# Booster_PA_PREAMP_HL.net
KiCad netlist of a schematic drawn in Altium Designer
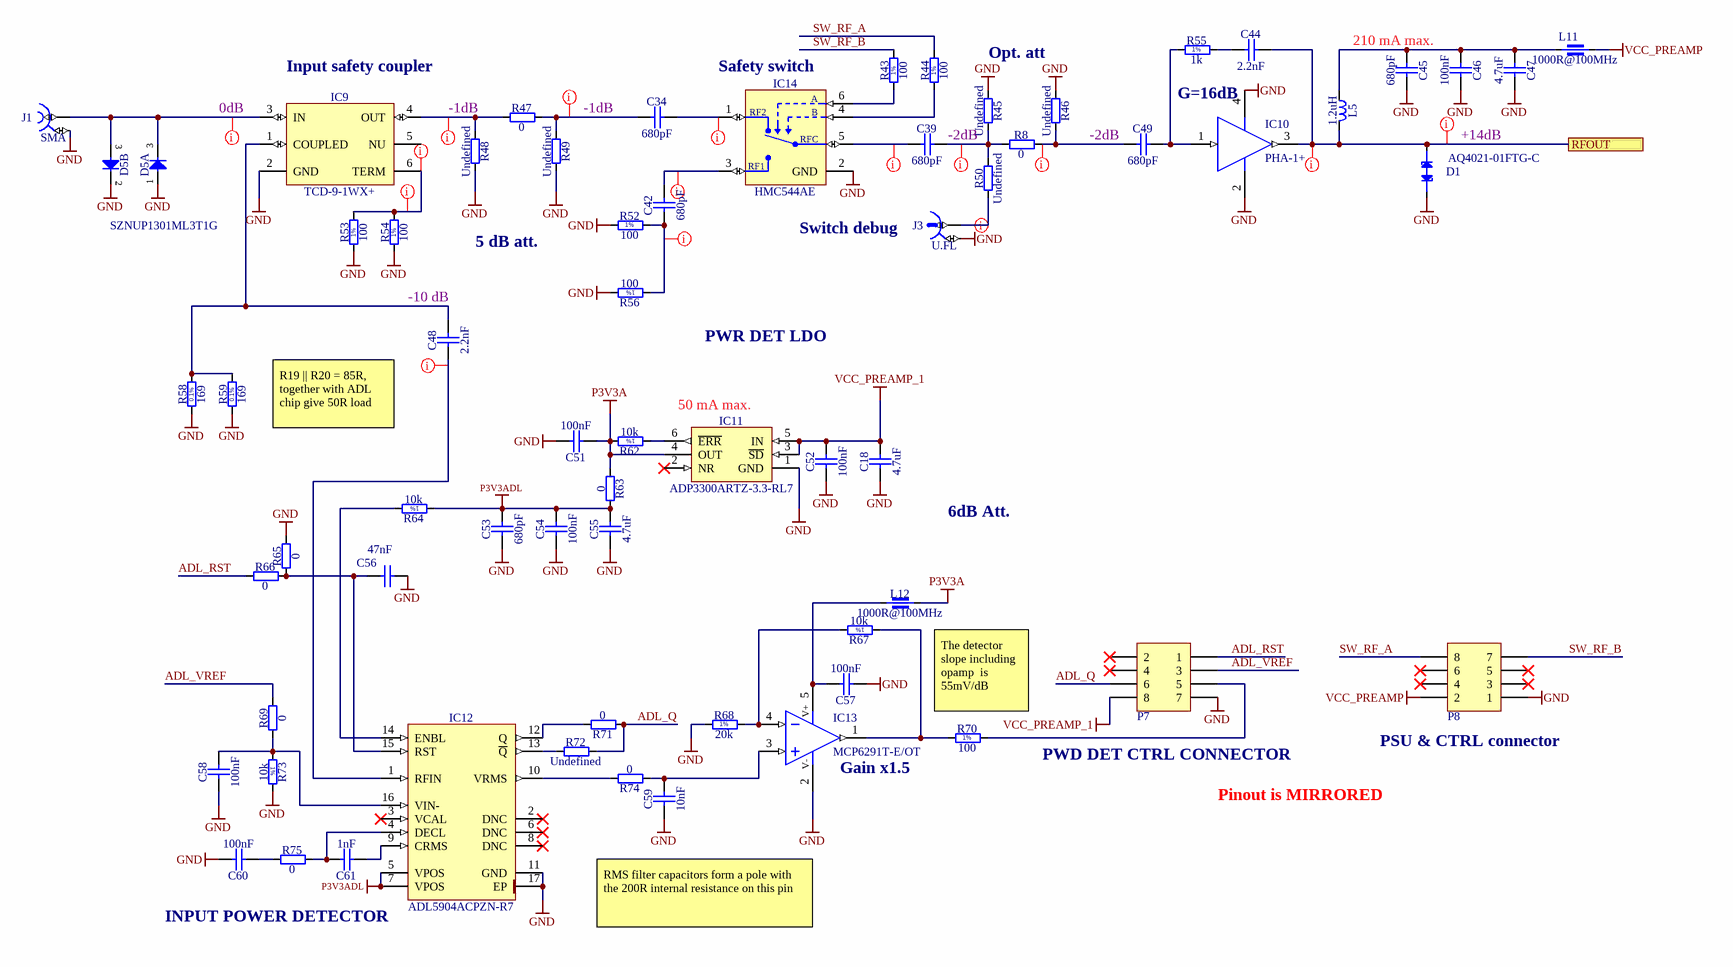
[diagram p0: Booster_PA_PREAMP_HL.SchDoc]

(export (version "E")
  (design (tool "Eeschema 10.0.6"))
  (components
    (comp (ref "C18")
      (value "4.7uF")
      (footprint "CAPC1709X95N")
      (description "Non-polarised capacitor")
      (fields
        (field (name "MANUFACTURER") "GENERIC")
        (field (name "MANUFACTURER PART NUMBER") "CC0603_4.7UF_16V_10%_X5R")
        (field (name "AUTHOR") "CERN DEM JLC")
      )
      (libsource (lib "Capacitors") (part "Capacitor - non polarized"))
    )
    (comp (ref "C34")
      (value "680pF")
      (footprint "CAPC1608X87N")
      (description "Non-polarised capacitor")
      (fields
        (field (name "PART NUMBER") "CC0603_680PF_50V_5%_NP0")
        (field (name "VOLTAGE") "50V")
        (field (name "AUTHOR") "CERN DEM JLC")
      )
      (libsource (lib "Capacitors") (part "Capacitor - non polarized"))
    )
    (comp (ref "C39")
      (value "680pF")
      (footprint "CAPC1608X87N")
      (description "Non-polarised capacitor")
      (fields
        (field (name "PART NUMBER") "CC0603_680PF_50V_5%_NP0")
        (field (name "VOLTAGE") "50V")
        (field (name "AUTHOR") "CERN DEM JLC")
      )
      (libsource (lib "Capacitors") (part "Capacitor - non polarized"))
    )
    (comp (ref "C42")
      (value "680pF")
      (footprint "CAPC1608X87N")
      (description "Non-polarised capacitor")
      (fields
        (field (name "PART NUMBER") "CC0603_680PF_50V_5%_NP0")
        (field (name "VOLTAGE") "50V")
        (field (name "AUTHOR") "CERN DEM JLC")
      )
      (libsource (lib "Capacitors") (part "Capacitor - non polarized"))
    )
    (comp (ref "C44")
      (value "2.2nF")
      (footprint "CAPC1608X87N")
      (description "Non-polarised capacitor")
      (fields
        (field (name "PART NUMBER") "CC0603_2.2NF_50V_5%_C0G")
        (field (name "VOLTAGE") "50V")
        (field (name "AUTHOR") "CERN DEM JMW")
      )
      (libsource (lib "Capacitors") (part "Capacitor - non polarized"))
    )
    (comp (ref "C45")
      (value "680pF")
      (footprint "CAPC1608X87N")
      (description "Non-polarised capacitor")
      (fields
        (field (name "MANUFACTURER") "GENERIC")
        (field (name "MANUFACTURER PART NUMBER") "CC0603_680PF_50V_5%_NP0")
        (field (name "AUTHOR") "CERN DEM JLC")
      )
      (libsource (lib "Capacitors") (part "Capacitor - non polarized"))
    )
    (comp (ref "C46")
      (value "100nF")
      (footprint "CAPC1608X87N")
      (description "Non-polarised capacitor")
      (fields
        (field (name "MANUFACTURER") "GENERIC")
        (field (name "MANUFACTURER PART NUMBER") "CC0603_100NF_50V_10%_X7R")
        (field (name "AUTHOR") "CERN DEM JLC")
      )
      (libsource (lib "Capacitors") (part "Capacitor - non polarized"))
    )
    (comp (ref "C47")
      (value "4.7uF")
      (footprint "CAPC1709X95N")
      (description "Non-polarised capacitor")
      (fields
        (field (name "MANUFACTURER") "GENERIC")
        (field (name "MANUFACTURER PART NUMBER") "CC0603_4.7UF_16V_10%_X5R")
        (field (name "AUTHOR") "CERN DEM JLC")
      )
      (libsource (lib "Capacitors") (part "Capacitor - non polarized"))
    )
    (comp (ref "C48")
      (value "2.2nF")
      (footprint "CAPC1608X87N")
      (description "Non-polarised capacitor")
      (fields
        (field (name "PART NUMBER") "CC0603_2.2NF_50V_5%_C0G")
        (field (name "VOLTAGE") "50V")
        (field (name "AUTHOR") "CERN DEM JMW")
      )
      (libsource (lib "Capacitors") (part "Capacitor - non polarized"))
    )
    (comp (ref "C49")
      (value "680pF")
      (footprint "CAPC1608X87N")
      (description "Non-polarised capacitor")
      (fields
        (field (name "MANUFACTURER") "GENERIC")
        (field (name "MANUFACTURER PART NUMBER") "CC0603_680PF_50V_5%_NP0")
        (field (name "AUTHOR") "CERN DEM JLC")
      )
      (libsource (lib "Capacitors") (part "Capacitor - non polarized"))
    )
    (comp (ref "C51")
      (value "100nF")
      (footprint "CAPC1608X87N")
      (description "Non-polarised capacitor")
      (fields
        (field (name "MANUFACTURER") "GENERIC")
        (field (name "MANUFACTURER PART NUMBER") "CC0603_100NF_50V_10%_X7R")
        (field (name "AUTHOR") "CERN DEM JLC")
      )
      (libsource (lib "Capacitors") (part "Capacitor - non polarized"))
    )
    (comp (ref "C52")
      (value "100nF")
      (footprint "CAPC1608X87N")
      (description "Non-polarised capacitor")
      (fields
        (field (name "MANUFACTURER") "GENERIC")
        (field (name "MANUFACTURER PART NUMBER") "CC0603_100NF_50V_10%_X7R")
        (field (name "AUTHOR") "CERN DEM JLC")
      )
      (libsource (lib "Capacitors") (part "Capacitor - non polarized"))
    )
    (comp (ref "C53")
      (value "680pF")
      (footprint "CAPC1608X87N")
      (description "Non-polarised capacitor")
      (fields
        (field (name "MANUFACTURER") "GENERIC")
        (field (name "MANUFACTURER PART NUMBER") "CC0603_680PF_50V_5%_NP0")
        (field (name "AUTHOR") "CERN DEM JLC")
      )
      (libsource (lib "Capacitors") (part "Capacitor - non polarized"))
    )
    (comp (ref "C54")
      (value "100nF")
      (footprint "CAPC1608X87N")
      (description "Non-polarised capacitor")
      (fields
        (field (name "MANUFACTURER") "GENERIC")
        (field (name "MANUFACTURER PART NUMBER") "CC0603_100NF_50V_10%_X7R")
        (field (name "AUTHOR") "CERN DEM JLC")
      )
      (libsource (lib "Capacitors") (part "Capacitor - non polarized"))
    )
    (comp (ref "C55")
      (value "4.7uF")
      (footprint "CAPC1709X95N")
      (description "Non-polarised capacitor")
      (fields
        (field (name "MANUFACTURER") "GENERIC")
        (field (name "MANUFACTURER PART NUMBER") "CC0603_4.7UF_16V_10%_X5R")
        (field (name "AUTHOR") "CERN DEM JLC")
      )
      (libsource (lib "Capacitors") (part "Capacitor - non polarized"))
    )
    (comp (ref "C56")
      (value "47nF")
      (footprint "CAPC1608X87N")
      (description "Non-polarised capacitor")
      (fields
        (field (name "PART NUMBER") "CC0603_47NF_25V_10%_X7R")
        (field (name "VOLTAGE") "25V")
        (field (name "AUTHOR") "CERN DEM JLC")
      )
      (libsource (lib "Capacitors") (part "Capacitor - non polarized"))
    )
    (comp (ref "C57")
      (value "100nF")
      (footprint "CAPC1608X87N")
      (description "Non-polarised capacitor")
      (fields
        (field (name "MANUFACTURER") "GENERIC")
        (field (name "MANUFACTURER PART NUMBER") "CC0603_100NF_50V_10%_X7R")
        (field (name "AUTHOR") "CERN DEM JLC")
      )
      (libsource (lib "Capacitors") (part "Capacitor - non polarized"))
    )
    (comp (ref "C58")
      (value "100nF")
      (footprint "CAPC1608X87N")
      (description "Non-polarised capacitor")
      (fields
        (field (name "MANUFACTURER") "GENERIC")
        (field (name "MANUFACTURER PART NUMBER") "CC0603_100NF_50V_10%_X7R")
        (field (name "AUTHOR") "CERN DEM JLC")
      )
      (libsource (lib "Capacitors") (part "Capacitor - non polarized"))
    )
    (comp (ref "C59")
      (value "10nF")
      (footprint "CAPC1005X55N")
      (description "Non-polarised capacitor")
      (fields
        (field (name "MANUFACTURER") "GENERIC")
        (field (name "MANUFACTURER PART NUMBER") "CC0402_10NF_25V_10%_X7R")
        (field (name "AUTHOR") "CERN DEM JLC")
      )
      (libsource (lib "Capacitors") (part "Capacitor - non polarized"))
    )
    (comp (ref "C60")
      (value "100nF")
      (footprint "CAPC1608X87N")
      (description "Non-polarised capacitor")
      (fields
        (field (name "MANUFACTURER") "GENERIC")
        (field (name "MANUFACTURER PART NUMBER") "CC0603_100NF_50V_10%_X7R")
        (field (name "AUTHOR") "CERN DEM JLC")
      )
      (libsource (lib "Capacitors") (part "Capacitor - non polarized"))
    )
    (comp (ref "C61")
      (value "1nF")
      (footprint "CAPC1005X55N")
      (description "Non-polarised capacitor")
      (fields
        (field (name "PART NUMBER") "CC0402_1NF_50V_10%_X7R")
        (field (name "VOLTAGE") "50V")
        (field (name "AUTHOR") "CERN DEM JLC")
      )
      (libsource (lib "Capacitors") (part "Capacitor - non polarized"))
    )
    (comp (ref "D1")
      (value "AQ4021-01FTG-C")
      (footprint "SOD2513X114N")
      (description "6V Bi-directional,ESD Protection for Transient Voltage Suppressor Diode")
      (fields (field (name "VOLTAGE") "6V") (field (name "POWER") "450W") (field (name "AUTHOR") "GK"))
      (libsource (lib "Diodes") (part "D_TVS_AQ4021-01FTG-C"))
    )
    (comp (ref "D5")
      (value "SZNUP1301ML3T1G")
      (footprint "SOT95P240X110-3N")
      (description "Low Capacitance Diode Array for ESD Protection in a Single Data Line")
      (fields (field (name "VOLTAGE") "70V") (field (name "POWER") "215mA") (field (name "AUTHOR") "GK"))
      (libsource (lib "Diodes") (part "D_TVS_SZNUP1301ML3T1G"))
    )
    (comp (ref "IC9")
      (value "TCD-9-1WX+")
      (footprint "MINI-CIRCUITS_DB1627")
      (description "50 Ohm, 5 To 2000MHz, Directional Coupler")
      (fields (field (name "MANUFACTURER") "MINI-CIRCUITS") (field (name "AUTHOR") "CERN DEM BC"))
      (libsource (lib "ICs And Semiconductors") (part "TCD-9-1W"))
    )
    (comp (ref "IC10")
      (value "PHA-1+")
      (footprint "MINI-CIRCUITS_DF782")
      (description "Monolithic Amplifier")
      (fields (field (name "MANUFACTURER") "MINI-CIRCUITS") (field (name "AUTHOR") "CERN DEM BC"))
      (libsource (lib "ICs And Semiconductors") (part "Monolithic Amplifier Type 1"))
    )
    (comp (ref "IC11")
      (value "ADP3300ARTZ-3.3-RL7")
      (footprint "SOT95P280X145-6N")
      (description "High Accuracy anyCAP® 50 mA Low Dropout Linear Regulator")
      (fields (field (name "MANUFACTURER") "ANALOG DEVICES") (field (name "AUTHOR") "CERN DEM JLC"))
      (libsource (lib "ICs And Semiconductors") (part "ADP3300ARTZ"))
    )
    (comp (ref "IC12")
      (value "ADL5904ACPZN-R7")
      (footprint "QFN50P300X300X80-17N-S175")
      (description "DC to 6 GHz, 45 dB TruPwr Detector With Envelope Threshold Detection")
      (fields (field (name "MANUFACTURER") "ANALOG DEVICES") (field (name "AUTHOR") "CERN DEM MR"))
      (libsource (lib "ICs And Semiconductors") (part "ADL5904"))
    )
    (comp (ref "IC13")
      (value "MCP6291T-E/OT")
      (footprint "SOT95P270X145-5N")
      (description "Operational Amplifier")
      (fields (field (name "MANUFACTURER") "MICROCHIP TECHNOLOGY") (field (name "AUTHOR") "CERN DEM BC"))
      (libsource (lib "ICs And Semiconductors") (part "Operational Amplifier Type7"))
    )
    (comp (ref "IC14")
      (value "HMC544AE")
      (footprint "SOT95P280X145-6N")
      (description "GaAs MMIC T/R Switch DC - 4 GHz")
      (fields (field (name "MANUFACTURER") "ANALOG DEVICES") (field (name "AUTHOR") "CERN DEM MR"))
      (libsource (lib "ICs And Semiconductors") (part "HMC544AE"))
    )
    (comp (ref "J1")
      (value "SMA")
      (footprint "LINK_CONSMA002-SMD-G")
      (fields
        (field (name "PART NUMBER") "LINK_CONSMA002-SMD-G")
        (field (name "MANUFACTURER") "LINK TECHNOLOGIES")
        (field (name "MANUFACTURER PART NUMBER") "CONSMA002-SMD-G")
        (field (name "AUTHOR") "CERN DEM BC")
      )
      (libsource (lib "Connectors") (part "Coax_1Female_1Shield"))
    )
    (comp (ref "J3")
      (value "U.FL")
      (footprint "HIROSE_U.FL-R-SMT-1(10)")
      (fields
        (field (name "PART NUMBER") "HIROSE_U.FL-R-SMT-1(10)")
        (field (name "MANUFACTURER") "HIROSE (HRS)")
        (field (name "MANUFACTURER PART NUMBER") "U.FL-R-SMT-1(10)")
        (field (name "AUTHOR") "CERN DEM JLC")
      )
      (libsource (lib "Connectors") (part "Coax_1Male_1Shield"))
    )
    (comp (ref "L5")
      (value "1.2uH")
      (footprint "IND_TDK_ADL2012")
      (description "Inductor")
      (fields
        (field (name "PART NUMBER") "IND0805_TDK_ADL2012S-1R2M-T01")
        (field (name "POWER") "400mA")
        (field (name "AUTHOR") "GK")
      )
      (libsource (lib "Inductors_Transformers") (part "IND0805_TDK_ADL2012S-1R2M-T01"))
    )
    (comp (ref "L11")
      (value "1000R@100MHz")
      (footprint "INDC1608X95N")
      (fields
        (field (name "MANUFACTURER") "MURATA")
        (field (name "MANUFACTURER PART NUMBER") "BLM18HE102SN1")
        (field (name "PART NUMBER") "IND0603_MURATA_BLM18HE102SN1")
        (field (name "AUTHOR") "CERN DEM JLC")
      )
      (libsource (lib "Inductors & Transformers") (part "Ferrite Bead"))
    )
    (comp (ref "L12")
      (value "1000R@100MHz")
      (footprint "INDC1608X95N")
      (fields
        (field (name "MANUFACTURER") "MURATA")
        (field (name "MANUFACTURER PART NUMBER") "BLM18HE102SN1")
        (field (name "PART NUMBER") "IND0603_MURATA_BLM18HE102SN1")
        (field (name "AUTHOR") "CERN DEM JLC")
      )
      (libsource (lib "Inductors & Transformers") (part "Ferrite Bead"))
    )
    (comp (ref "P7")
      (value "ZL264-8DG")
      (footprint "HDR2X4_SMD")
      (description "Header, 4-Pin, Dual Row")
      (libsource (lib "onyks") (part "HDR2X4"))
    )
    (comp (ref "P8")
      (value "ZL264-8DG")
      (footprint "HDR2X4_SMD")
      (description "Header, 4-Pin, Dual Row")
      (libsource (lib "") (part "HDR2X4_1"))
    )
    (comp (ref "R8")
      (value "0")
      (footprint "RESC1608X55N")
      (description "Resistor")
      (fields
        (field (name "MANUFACTURER") "GENERIC")
        (field (name "MANUFACTURER PART NUMBER") "R0603_0R_JUMPER")
        (field (name "AUTHOR") "CERN DEM JLC")
      )
      (libsource (lib "Resistors") (part "Resistor"))
    )
    (comp (ref "R43")
      (value "100")
      (footprint "RESC1608X55N")
      (description "Resistor - 1%")
      (fields
        (field (name "MANUFACTURER") "GENERIC")
        (field (name "MANUFACTURER PART NUMBER") "R0603_100R_1%_0.1W_100PPM")
        (field (name "AUTHOR") "CERN DEM JLC")
      )
      (libsource (lib "Resistors") (part "Resistor - 1%"))
    )
    (comp (ref "R44")
      (value "100")
      (footprint "RESC1608X55N")
      (description "Resistor - 1%")
      (fields
        (field (name "MANUFACTURER") "GENERIC")
        (field (name "MANUFACTURER PART NUMBER") "R0603_100R_1%_0.1W_100PPM")
        (field (name "AUTHOR") "CERN DEM JLC")
      )
      (libsource (lib "Resistors") (part "Resistor - 1%"))
    )
    (comp (ref "R45")
      (value "Undefined")
      (footprint "RESC1608X55N")
      (description "Resistor")
      (fields
        (field (name "MANUFACTURER PART NUMBER") "R0603_NO-VALUE")
        (field (name "AUTHOR") "CERN DEM JLC")
      )
      (libsource (lib "Resistors") (part "Resistor"))
    )
    (comp (ref "R46")
      (value "Undefined")
      (footprint "RESC1608X55N")
      (description "Resistor")
      (fields
        (field (name "MANUFACTURER PART NUMBER") "R0603_NO-VALUE")
        (field (name "AUTHOR") "CERN DEM JLC")
      )
      (libsource (lib "Resistors") (part "Resistor"))
    )
    (comp (ref "R47")
      (value "0")
      (footprint "RESC1608X55N")
      (description "Resistor")
      (fields
        (field (name "PART NUMBER") "R0603_0R_JUMPER")
        (field (name "MANUFACTURER") "GENERIC")
        (field (name "AUTHOR") "CERN DEM JLC")
      )
      (libsource (lib "Resistors") (part "Resistor"))
    )
    (comp (ref "R48")
      (value "Undefined")
      (footprint "RESC1608X55N")
      (description "Resistor")
      (fields
        (field (name "MANUFACTURER PART NUMBER") "R0603_NO-VALUE")
        (field (name "AUTHOR") "CERN DEM JLC")
      )
      (libsource (lib "Resistors") (part "Resistor"))
    )
    (comp (ref "R49")
      (value "Undefined")
      (footprint "RESC1608X55N")
      (description "Resistor")
      (fields
        (field (name "MANUFACTURER PART NUMBER") "R0603_NO-VALUE")
        (field (name "AUTHOR") "CERN DEM JLC")
      )
      (libsource (lib "Resistors") (part "Resistor"))
    )
    (comp (ref "R50")
      (value "Undefined")
      (footprint "RESC1608X55N")
      (description "Resistor")
      (fields
        (field (name "MANUFACTURER PART NUMBER") "R0603_NO-VALUE")
        (field (name "AUTHOR") "CERN DEM JLC")
      )
      (libsource (lib "Resistors") (part "Resistor"))
    )
    (comp (ref "R52")
      (value "100")
      (footprint "RESC1608X55N")
      (description "Resistor - 1%")
      (fields
        (field (name "MANUFACTURER") "GENERIC")
        (field (name "MANUFACTURER PART NUMBER") "R0603_100R_1%_0.1W_100PPM")
        (field (name "AUTHOR") "CERN DEM JLC")
      )
      (libsource (lib "Resistors") (part "Resistor - 1%"))
    )
    (comp (ref "R53")
      (value "100")
      (footprint "RESC1608X55N")
      (description "Resistor - 1%")
      (fields
        (field (name "MANUFACTURER") "GENERIC")
        (field (name "MANUFACTURER PART NUMBER") "R0603_100R_1%_0.1W_100PPM")
        (field (name "AUTHOR") "CERN DEM JLC")
      )
      (libsource (lib "Resistors") (part "Resistor - 1%"))
    )
    (comp (ref "R54")
      (value "100")
      (footprint "RESC1608X55N")
      (description "Resistor - 1%")
      (fields
        (field (name "MANUFACTURER") "GENERIC")
        (field (name "MANUFACTURER PART NUMBER") "R0603_100R_1%_0.1W_100PPM")
        (field (name "AUTHOR") "CERN DEM JLC")
      )
      (libsource (lib "Resistors") (part "Resistor - 1%"))
    )
    (comp (ref "R55")
      (value "1k")
      (footprint "RESC1608X55N")
      (description "Resistor - 1%")
      (fields
        (field (name "MANUFACTURER") "GENERIC")
        (field (name "MANUFACTURER PART NUMBER") "R0603_1K_1%_0.1W_100PPM")
        (field (name "AUTHOR") "CERN DEM JLC")
      )
      (libsource (lib "Resistors") (part "Resistor - 1%"))
    )
    (comp (ref "R56")
      (value "100")
      (footprint "RESC1608X55N")
      (description "Resistor - 1%")
      (fields
        (field (name "MANUFACTURER") "GENERIC")
        (field (name "MANUFACTURER PART NUMBER") "R0603_100R_1%_0.1W_100PPM")
        (field (name "AUTHOR") "CERN DEM JLC")
      )
      (libsource (lib "Resistors") (part "Resistor - 1%"))
    )
    (comp (ref "R58")
      (value "169")
      (footprint "RESC1608X55N")
      (description "Resistor - 0.1%")
      (fields
        (field (name "PART NUMBER") "R0603_169R_0.1%_0.063W_10PPM")
        (field (name "POWER") "0.063W")
        (field (name "AUTHOR") "CERN DEM JLC")
      )
      (libsource (lib "Resistors") (part "Resistor - 0.1%"))
    )
    (comp (ref "R59")
      (value "169")
      (footprint "RESC1608X55N")
      (description "Resistor - 0.1%")
      (fields
        (field (name "PART NUMBER") "R0603_169R_0.1%_0.063W_10PPM")
        (field (name "POWER") "0.063W")
        (field (name "AUTHOR") "CERN DEM JLC")
      )
      (libsource (lib "Resistors") (part "Resistor - 0.1%"))
    )
    (comp (ref "R62")
      (value "10k")
      (footprint "RESC1005X40N")
      (description "Resistor - 1%")
      (fields
        (field (name "MANUFACTURER") "GENERIC")
        (field (name "MANUFACTURER PART NUMBER") "R0402_10K_1%_0.0625W_100PPM")
        (field (name "AUTHOR") "CERN DEM JLC")
      )
      (libsource (lib "Resistors") (part "Resistor - 1%"))
    )
    (comp (ref "R63")
      (value "0")
      (footprint "RESC1005X40N")
      (description "Resistor")
      (fields
        (field (name "MANUFACTURER") "GENERIC")
        (field (name "MANUFACTURER PART NUMBER") "R0402_0R_JUMPER")
        (field (name "AUTHOR") "CERN DEM JLC")
      )
      (libsource (lib "Resistors") (part "Resistor"))
    )
    (comp (ref "R64")
      (value "10k")
      (footprint "RESC1005X40N")
      (description "Resistor - 1%")
      (fields
        (field (name "MANUFACTURER") "GENERIC")
        (field (name "MANUFACTURER PART NUMBER") "R0402_10K_1%_0.0625W_100PPM")
        (field (name "AUTHOR") "CERN DEM JLC")
      )
      (libsource (lib "Resistors") (part "Resistor - 1%"))
    )
    (comp (ref "R65")
      (value "0")
      (footprint "RESC1608X55N")
      (description "Resistor")
      (fields
        (field (name "MANUFACTURER") "GENERIC")
        (field (name "MANUFACTURER PART NUMBER") "R0603_0R_JUMPER")
        (field (name "AUTHOR") "CERN DEM JLC")
      )
      (libsource (lib "Resistors") (part "Resistor"))
    )
    (comp (ref "R66")
      (value "0")
      (footprint "RESC1005X40N")
      (description "Resistor")
      (fields
        (field (name "MANUFACTURER") "GENERIC")
        (field (name "MANUFACTURER PART NUMBER") "R0402_0R_JUMPER")
        (field (name "AUTHOR") "CERN DEM JLC")
      )
      (libsource (lib "Resistors") (part "Resistor"))
    )
    (comp (ref "R67")
      (value "10k")
      (footprint "RESC1005X40N")
      (description "Resistor - 1%")
      (fields
        (field (name "MANUFACTURER") "GENERIC")
        (field (name "MANUFACTURER PART NUMBER") "R0402_10K_1%_0.0625W_100PPM")
        (field (name "AUTHOR") "CERN DEM JLC")
      )
      (libsource (lib "Resistors") (part "Resistor - 1%"))
    )
    (comp (ref "R68")
      (value "20k")
      (footprint "RESC1608X55N")
      (description "Resistor - 1%")
      (fields
        (field (name "PART NUMBER") "R0603_20K_1%_0.1W_100PPM")
        (field (name "POWER") "0.1W")
        (field (name "AUTHOR") "CERN DEM JLC")
      )
      (libsource (lib "Resistors") (part "Resistor - 1%"))
    )
    (comp (ref "R69")
      (value "0")
      (footprint "RESC1608X55N")
      (description "Resistor")
      (fields
        (field (name "MANUFACTURER") "GENERIC")
        (field (name "MANUFACTURER PART NUMBER") "R0603_0R_JUMPER")
        (field (name "AUTHOR") "CERN DEM JLC")
      )
      (libsource (lib "Resistors") (part "Resistor"))
    )
    (comp (ref "R70")
      (value "100")
      (footprint "RESC1608X55N")
      (description "Resistor - 1%")
      (fields
        (field (name "MANUFACTURER") "GENERIC")
        (field (name "MANUFACTURER PART NUMBER") "R0603_100R_1%_0.1W_100PPM")
        (field (name "AUTHOR") "CERN DEM JLC")
      )
      (libsource (lib "Resistors") (part "Resistor - 1%"))
    )
    (comp (ref "R71")
      (value "0")
      (footprint "RESC1005X40N")
      (description "Resistor")
      (fields
        (field (name "MANUFACTURER") "GENERIC")
        (field (name "MANUFACTURER PART NUMBER") "R0402_0R_JUMPER")
        (field (name "AUTHOR") "CERN DEM JLC")
      )
      (libsource (lib "Resistors") (part "Resistor"))
    )
    (comp (ref "R72")
      (value "Undefined")
      (footprint "RESC1608X55N")
      (description "Resistor")
      (fields
        (field (name "MANUFACTURER PART NUMBER") "R0603_NO-VALUE")
        (field (name "AUTHOR") "CERN DEM JLC")
      )
      (libsource (lib "Resistors") (part "Resistor"))
    )
    (comp (ref "R73")
      (value "10k")
      (footprint "RESC1005X40N")
      (description "Resistor - 1%")
      (fields
        (field (name "MANUFACTURER") "GENERIC")
        (field (name "MANUFACTURER PART NUMBER") "R0402_10K_1%_0.0625W_100PPM")
        (field (name "AUTHOR") "CERN DEM JLC")
      )
      (libsource (lib "Resistors") (part "Resistor - 1%"))
    )
    (comp (ref "R74")
      (value "0")
      (footprint "RESC1005X40N")
      (description "Resistor")
      (fields
        (field (name "MANUFACTURER") "GENERIC")
        (field (name "MANUFACTURER PART NUMBER") "R0402_0R_JUMPER")
        (field (name "AUTHOR") "CERN DEM JLC")
      )
      (libsource (lib "Resistors") (part "Resistor"))
    )
    (comp (ref "R75")
      (value "0")
      (footprint "RESC1005X40N")
      (description "Resistor")
      (fields
        (field (name "MANUFACTURER") "GENERIC")
        (field (name "MANUFACTURER PART NUMBER") "R0402_0R_JUMPER")
        (field (name "AUTHOR") "CERN DEM JLC")
      )
      (libsource (lib "Resistors") (part "Resistor"))
    )
  )
  (nets
    (net (code "1") (name "/ADL_Q") (class "Default")
      (node (ref "P7") (pin "6") (pinfunction "6_6") (pintype "passive"))
      (node (ref "R71") (pin "1") (pinfunction "1_1") (pintype "passive"))
      (node (ref "R72") (pin "2") (pinfunction "2_2") (pintype "passive"))
    )
    (net (code "2") (name "/ADL_RST") (class "Default")
      (node (ref "P7") (pin "1") (pinfunction "1_1") (pintype "passive"))
      (node (ref "R66") (pin "1") (pinfunction "1_1") (pintype "passive"))
    )
    (net (code "3") (name "/ADL_VREF") (class "Default")
      (node (ref "P7") (pin "3") (pinfunction "3_3") (pintype "passive"))
      (node (ref "R69") (pin "2") (pinfunction "2_2") (pintype "passive"))
    )
    (net (code "4") (name "/RFOUT") (class "Default")
      (node (ref "C44") (pin "2") (pinfunction "2_2") (pintype "passive"))
      (node (ref "D1") (pin "1") (pinfunction "C_1") (pintype "passive"))
      (node (ref "IC10") (pin "3") (pinfunction "RF_OUT_3") (pintype "output"))
      (node (ref "L5") (pin "2") (pinfunction "2_2") (pintype "passive"))
    )
    (net (code "5") (name "/SW_RF_A") (class "Default")
      (node (ref "P8") (pin "8") (pinfunction "8_8") (pintype "passive"))
      (node (ref "R44") (pin "2") (pinfunction "2_2") (pintype "passive"))
    )
    (net (code "6") (name "/SW_RF_B") (class "Default")
      (node (ref "P8") (pin "7") (pinfunction "7_7") (pintype "passive"))
      (node (ref "R43") (pin "2") (pinfunction "2_2") (pintype "passive"))
    )
    (net (code "7") (name "GND") (class "Default")
      (node (ref "C18") (pin "1") (pinfunction "1_1") (pintype "passive"))
      (node (ref "C45") (pin "1") (pinfunction "1_1") (pintype "passive"))
      (node (ref "C46") (pin "1") (pinfunction "1_1") (pintype "passive"))
      (node (ref "C47") (pin "1") (pinfunction "1_1") (pintype "passive"))
      (node (ref "C51") (pin "2") (pinfunction "2_2") (pintype "passive"))
      (node (ref "C52") (pin "1") (pinfunction "1_1") (pintype "passive"))
      (node (ref "C53") (pin "1") (pinfunction "1_1") (pintype "passive"))
      (node (ref "C54") (pin "1") (pinfunction "1_1") (pintype "passive"))
      (node (ref "C55") (pin "1") (pinfunction "1_1") (pintype "passive"))
      (node (ref "C56") (pin "2") (pinfunction "2_2") (pintype "passive"))
      (node (ref "C57") (pin "1") (pinfunction "1_1") (pintype "passive"))
      (node (ref "C58") (pin "1") (pinfunction "1_1") (pintype "passive"))
      (node (ref "C59") (pin "1") (pinfunction "1_1") (pintype "passive"))
      (node (ref "C60") (pin "2") (pinfunction "2_2") (pintype "passive"))
      (node (ref "D1") (pin "2") (pinfunction "A_2") (pintype "passive"))
      (node (ref "D5") (pin "1") (pinfunction "A_1") (pintype "passive"))
      (node (ref "D5") (pin "2") (pinfunction "C_2") (pintype "passive"))
      (node (ref "IC10") (pin "2") (pinfunction "GND_2") (pintype "power_in"))
      (node (ref "IC10") (pin "4") (pinfunction "GND_4") (pintype "power_in"))
      (node (ref "IC11") (pin "1") (pinfunction "GND_1") (pintype "power_in"))
      (node (ref "IC12") (pin "11") (pinfunction "GND_11") (pintype "power_in"))
      (node (ref "IC12") (pin "17") (pinfunction "EP_17") (pintype "power_in"))
      (node (ref "IC13") (pin "2") (pinfunction "V-_2") (pintype "power_in"))
      (node (ref "IC14") (pin "2") (pinfunction "GND_2") (pintype "power_in"))
      (node (ref "IC9") (pin "2") (pinfunction "GND_2") (pintype "power_in"))
      (node (ref "J1") (pin "2") (pinfunction "2_2") (pintype "bidirectional"))
      (node (ref "J3") (pin "2") (pinfunction "2_2") (pintype "bidirectional"))
      (node (ref "P7") (pin "7") (pinfunction "7_7") (pintype "passive"))
      (node (ref "P8") (pin "1") (pinfunction "1_1") (pintype "passive"))
      (node (ref "R45") (pin "1") (pinfunction "1_1") (pintype "passive"))
      (node (ref "R46") (pin "1") (pinfunction "1_1") (pintype "passive"))
      (node (ref "R48") (pin "2") (pinfunction "2_2") (pintype "passive"))
      (node (ref "R49") (pin "2") (pinfunction "2_2") (pintype "passive"))
      (node (ref "R52") (pin "1") (pinfunction "1_1") (pintype "passive"))
      (node (ref "R53") (pin "1") (pinfunction "1_1") (pintype "passive"))
      (node (ref "R54") (pin "1") (pinfunction "1_1") (pintype "passive"))
      (node (ref "R56") (pin "2") (pinfunction "2_2") (pintype "passive"))
      (node (ref "R58") (pin "1") (pinfunction "1_1") (pintype "passive"))
      (node (ref "R59") (pin "1") (pinfunction "1_1") (pintype "passive"))
      (node (ref "R65") (pin "2") (pinfunction "2_2") (pintype "passive"))
      (node (ref "R68") (pin "1") (pinfunction "1_1") (pintype "passive"))
      (node (ref "R73") (pin "2") (pinfunction "2_2") (pintype "passive"))
    )
    (net (code "8") (name "Net-(C34-Pad1)") (class "Default")
      (node (ref "C34") (pin "1") (pinfunction "1_1") (pintype "passive"))
      (node (ref "R47") (pin "2") (pinfunction "2_2") (pintype "passive"))
      (node (ref "R49") (pin "1") (pinfunction "1_1") (pintype "passive"))
    )
    (net (code "9") (name "Net-(C39-Pad2)") (class "Default")
      (node (ref "C39") (pin "2") (pinfunction "2_2") (pintype "passive"))
      (node (ref "R45") (pin "2") (pinfunction "2_2") (pintype "passive"))
      (node (ref "R50") (pin "2") (pinfunction "2_2") (pintype "passive"))
      (node (ref "R8") (pin "1") (pinfunction "1_1") (pintype "passive"))
    )
    (net (code "10") (name "Net-(C42-Pad1)") (class "Default")
      (node (ref "C42") (pin "1") (pinfunction "1_1") (pintype "passive"))
      (node (ref "R52") (pin "2") (pinfunction "2_2") (pintype "passive"))
      (node (ref "R56") (pin "1") (pinfunction "1_1") (pintype "passive"))
    )
    (net (code "11") (name "Net-(C44-Pad1)") (class "Default")
      (node (ref "C44") (pin "1") (pinfunction "1_1") (pintype "passive"))
      (node (ref "R55") (pin "2") (pinfunction "2_2") (pintype "passive"))
    )
    (net (code "12") (name "Net-(C45-Pad2)") (class "Default")
      (node (ref "C45") (pin "2") (pinfunction "2_2") (pintype "passive"))
      (node (ref "C46") (pin "2") (pinfunction "2_2") (pintype "passive"))
      (node (ref "C47") (pin "2") (pinfunction "2_2") (pintype "passive"))
      (node (ref "L11") (pin "1") (pinfunction "1_1") (pintype "passive"))
      (node (ref "L5") (pin "1") (pinfunction "1_1") (pintype "passive"))
    )
    (net (code "13") (name "Net-(C49-Pad1)") (class "Default")
      (node (ref "C49") (pin "1") (pinfunction "1_1") (pintype "passive"))
      (node (ref "R46") (pin "2") (pinfunction "2_2") (pintype "passive"))
      (node (ref "R8") (pin "2") (pinfunction "2_2") (pintype "passive"))
    )
    (net (code "14") (name "Net-(C60-Pad1)") (class "Default")
      (node (ref "C60") (pin "1") (pinfunction "1_1") (pintype "passive"))
      (node (ref "R75") (pin "1") (pinfunction "1_1") (pintype "passive"))
    )
    (net (code "15") (name "Net-(D5A-COMAC)") (class "Default")
      (node (ref "D5") (pin "3") (pinfunction "COMAC_3") (pintype "passive"))
      (node (ref "IC9") (pin "3") (pinfunction "IN_3") (pintype "bidirectional"))
      (node (ref "J1") (pin "1") (pinfunction "1_1") (pintype "bidirectional"))
    )
    (net (code "16") (name "Net-(IC9-COUPLED)") (class "Default")
      (node (ref "C48") (pin "2") (pinfunction "2_2") (pintype "passive"))
      (node (ref "IC9") (pin "1") (pinfunction "COUPLED_1") (pintype "bidirectional"))
      (node (ref "R58") (pin "2") (pinfunction "2_2") (pintype "passive"))
      (node (ref "R59") (pin "2") (pinfunction "2_2") (pintype "passive"))
    )
    (net (code "17") (name "Net-(IC9-OUT)") (class "Default")
      (node (ref "IC9") (pin "4") (pinfunction "OUT_4") (pintype "bidirectional"))
      (node (ref "R47") (pin "1") (pinfunction "1_1") (pintype "passive"))
      (node (ref "R48") (pin "1") (pinfunction "1_1") (pintype "passive"))
    )
    (net (code "18") (name "Net-(IC9-TERM)") (class "Default")
      (node (ref "IC9") (pin "6") (pinfunction "TERM_6") (pintype "passive"))
      (node (ref "R53") (pin "2") (pinfunction "2_2") (pintype "passive"))
      (node (ref "R54") (pin "2") (pinfunction "2_2") (pintype "passive"))
    )
    (net (code "19") (name "Net-(IC10-RF_IN)") (class "Default")
      (node (ref "C49") (pin "2") (pinfunction "2_2") (pintype "passive"))
      (node (ref "IC10") (pin "1") (pinfunction "RF_IN_1") (pintype "input"))
      (node (ref "R55") (pin "1") (pinfunction "1_1") (pintype "passive"))
    )
    (net (code "20") (name "Net-(IC11-~{ERR})") (class "Default")
      (node (ref "IC11") (pin "6") (pinfunction "~{ERR}_6") (pintype "output"))
      (node (ref "R62") (pin "1") (pinfunction "1_1") (pintype "passive"))
    )
    (net (code "21") (name "Net-(IC12-CRMS)") (class "Default")
      (node (ref "C61") (pin "1") (pinfunction "1_1") (pintype "passive"))
      (node (ref "IC12") (pin "9") (pinfunction "CRMS_9") (pintype "input"))
    )
    (net (code "22") (name "Net-(IC12-DECL)") (class "Default")
      (node (ref "C61") (pin "2") (pinfunction "2_2") (pintype "passive"))
      (node (ref "IC12") (pin "4") (pinfunction "DECL_4") (pintype "input"))
      (node (ref "R75") (pin "2") (pinfunction "2_2") (pintype "passive"))
    )
    (net (code "23") (name "Net-(IC12-ENBL)") (class "Default")
      (node (ref "IC12") (pin "14") (pinfunction "ENBL_14") (pintype "input"))
      (node (ref "R64") (pin "2") (pinfunction "2_2") (pintype "passive"))
    )
    (net (code "24") (name "Net-(IC12-Q)") (class "Default")
      (node (ref "IC12") (pin "12") (pinfunction "Q_12") (pintype "output"))
      (node (ref "R71") (pin "2") (pinfunction "2_2") (pintype "passive"))
    )
    (net (code "25") (name "Net-(IC12-RFIN)") (class "Default")
      (node (ref "C48") (pin "1") (pinfunction "1_1") (pintype "passive"))
      (node (ref "IC12") (pin "1") (pinfunction "RFIN_1") (pintype "input"))
    )
    (net (code "26") (name "Net-(IC12-RST)") (class "Default")
      (node (ref "C56") (pin "1") (pinfunction "1_1") (pintype "passive"))
      (node (ref "IC12") (pin "15") (pinfunction "RST_15") (pintype "input"))
      (node (ref "R65") (pin "1") (pinfunction "1_1") (pintype "passive"))
      (node (ref "R66") (pin "2") (pinfunction "2_2") (pintype "passive"))
    )
    (net (code "27") (name "Net-(IC12-VIN-)") (class "Default")
      (node (ref "C58") (pin "2") (pinfunction "2_2") (pintype "passive"))
      (node (ref "IC12") (pin "16") (pinfunction "VIN-_16") (pintype "input"))
      (node (ref "R69") (pin "1") (pinfunction "1_1") (pintype "passive"))
      (node (ref "R73") (pin "1") (pinfunction "1_1") (pintype "passive"))
    )
    (net (code "28") (name "Net-(IC12-VRMS)") (class "Default")
      (node (ref "IC12") (pin "10") (pinfunction "VRMS_10") (pintype "output"))
      (node (ref "R74") (pin "2") (pinfunction "2_2") (pintype "passive"))
    )
    (net (code "29") (name "Net-(IC12-~{Q})") (class "Default")
      (node (ref "IC12") (pin "13") (pinfunction "~{Q}_13") (pintype "output"))
      (node (ref "R72") (pin "1") (pinfunction "1_1") (pintype "passive"))
    )
    (net (code "30") (name "Net-(IC13-IN+)") (class "Default")
      (node (ref "C59") (pin "2") (pinfunction "2_2") (pintype "passive"))
      (node (ref "IC13") (pin "3") (pinfunction "IN+_3") (pintype "input"))
      (node (ref "R74") (pin "1") (pinfunction "1_1") (pintype "passive"))
    )
    (net (code "31") (name "Net-(IC13-IN-)") (class "Default")
      (node (ref "IC13") (pin "4") (pinfunction "IN-_4") (pintype "input"))
      (node (ref "R67") (pin "2") (pinfunction "2_2") (pintype "passive"))
      (node (ref "R68") (pin "2") (pinfunction "2_2") (pintype "passive"))
    )
    (net (code "32") (name "Net-(IC13-OUT)") (class "Default")
      (node (ref "IC13") (pin "1") (pinfunction "OUT_1") (pintype "output"))
      (node (ref "R67") (pin "1") (pinfunction "1_1") (pintype "passive"))
      (node (ref "R70") (pin "1") (pinfunction "1_1") (pintype "passive"))
    )
    (net (code "33") (name "Net-(IC13-V+)") (class "Default")
      (node (ref "C57") (pin "2") (pinfunction "2_2") (pintype "passive"))
      (node (ref "IC13") (pin "5") (pinfunction "V+_5") (pintype "power_in"))
      (node (ref "L12") (pin "1") (pinfunction "1_1") (pintype "passive"))
    )
    (net (code "34") (name "Net-(IC14-A)") (class "Default")
      (node (ref "IC14") (pin "6") (pinfunction "A_6") (pintype "input"))
      (node (ref "R43") (pin "1") (pinfunction "1_1") (pintype "passive"))
    )
    (net (code "35") (name "Net-(IC14-B)") (class "Default")
      (node (ref "IC14") (pin "4") (pinfunction "B_4") (pintype "input"))
      (node (ref "R44") (pin "1") (pinfunction "1_1") (pintype "passive"))
    )
    (net (code "36") (name "Net-(IC14-RF1)") (class "Default")
      (node (ref "C42") (pin "2") (pinfunction "2_2") (pintype "passive"))
      (node (ref "IC14") (pin "3") (pinfunction "RF1_3") (pintype "bidirectional"))
    )
    (net (code "37") (name "Net-(IC14-RF2)") (class "Default")
      (node (ref "C34") (pin "2") (pinfunction "2_2") (pintype "passive"))
      (node (ref "IC14") (pin "1") (pinfunction "RF2_1") (pintype "bidirectional"))
    )
    (net (code "38") (name "Net-(IC14-RFC)") (class "Default")
      (node (ref "C39") (pin "1") (pinfunction "1_1") (pintype "passive"))
      (node (ref "IC14") (pin "5") (pinfunction "RFC_5") (pintype "bidirectional"))
    )
    (net (code "39") (name "Net-(J3-Pad1)") (class "Default")
      (node (ref "J3") (pin "1") (pinfunction "1_1") (pintype "bidirectional"))
      (node (ref "R50") (pin "1") (pinfunction "1_1") (pintype "passive"))
    )
    (net (code "40") (name "Net-(P7-Pad5)") (class "Default")
      (node (ref "P7") (pin "5") (pinfunction "5_5") (pintype "passive"))
      (node (ref "R70") (pin "2") (pinfunction "2_2") (pintype "passive"))
    )
    (net (code "41") (name "P3V3A") (class "Default")
      (node (ref "C51") (pin "1") (pinfunction "1_1") (pintype "passive"))
      (node (ref "IC11") (pin "4") (pinfunction "OUT_4") (pintype "power_in"))
      (node (ref "L12") (pin "2") (pinfunction "2_2") (pintype "passive"))
      (node (ref "R62") (pin "2") (pinfunction "2_2") (pintype "passive"))
      (node (ref "R63") (pin "1") (pinfunction "1_1") (pintype "passive"))
    )
    (net (code "42") (name "P3V3ADL") (class "Default")
      (node (ref "C53") (pin "2") (pinfunction "2_2") (pintype "passive"))
      (node (ref "C54") (pin "2") (pinfunction "2_2") (pintype "passive"))
      (node (ref "C55") (pin "2") (pinfunction "2_2") (pintype "passive"))
      (node (ref "IC12") (pin "5") (pinfunction "VPOS_5") (pintype "power_in"))
      (node (ref "IC12") (pin "7") (pinfunction "VPOS_7") (pintype "power_in"))
      (node (ref "R63") (pin "2") (pinfunction "2_2") (pintype "passive"))
      (node (ref "R64") (pin "1") (pinfunction "1_1") (pintype "passive"))
    )
    (net (code "43") (name "VCC_PREAMP") (class "Default")
      (node (ref "L11") (pin "2") (pinfunction "2_2") (pintype "passive"))
      (node (ref "P8") (pin "2") (pinfunction "2_2") (pintype "passive"))
    )
    (net (code "44") (name "VCC_PREAMP_1") (class "Default")
      (node (ref "C18") (pin "2") (pinfunction "2_2") (pintype "passive"))
      (node (ref "C52") (pin "2") (pinfunction "2_2") (pintype "passive"))
      (node (ref "IC11") (pin "3") (pinfunction "~{SD}_3") (pintype "input"))
      (node (ref "IC11") (pin "5") (pinfunction "IN_5") (pintype "input"))
      (node (ref "P7") (pin "8") (pinfunction "8_8") (pintype "passive"))
    )
    (net (code "45") (name "unconnected-(IC9-NU-Pad5)") (class "Default")
      (node (ref "IC9") (pin "5") (pinfunction "NU_5") (pintype "passive"))
    )
    (net (code "46") (name "unconnected-(IC11-NR-Pad2)") (class "Default")
      (node (ref "IC11") (pin "2") (pinfunction "NR_2") (pintype "input+no_connect"))
    )
    (net (code "47") (name "unconnected-(IC12-DNC-Pad2)") (class "Default")
      (node (ref "IC12") (pin "2") (pinfunction "DNC_2") (pintype "passive+no_connect"))
    )
    (net (code "48") (name "unconnected-(IC12-DNC-Pad6)") (class "Default")
      (node (ref "IC12") (pin "6") (pinfunction "DNC_6") (pintype "passive+no_connect"))
    )
    (net (code "49") (name "unconnected-(IC12-DNC-Pad8)") (class "Default")
      (node (ref "IC12") (pin "8") (pinfunction "DNC_8") (pintype "passive+no_connect"))
    )
    (net (code "50") (name "unconnected-(IC12-VCAL-Pad3)") (class "Default")
      (node (ref "IC12") (pin "3") (pinfunction "VCAL_3") (pintype "input+no_connect"))
    )
    (net (code "51") (name "unconnected-(P7-Pad2)") (class "Default")
      (node (ref "P7") (pin "2") (pinfunction "2_2") (pintype "passive+no_connect"))
    )
    (net (code "52") (name "unconnected-(P7-Pad4)") (class "Default")
      (node (ref "P7") (pin "4") (pinfunction "4_4") (pintype "passive+no_connect"))
    )
    (net (code "53") (name "unconnected-(P8-Pad3)") (class "Default")
      (node (ref "P8") (pin "3") (pinfunction "3_3") (pintype "passive+no_connect"))
    )
    (net (code "54") (name "unconnected-(P8-Pad4)") (class "Default")
      (node (ref "P8") (pin "4") (pinfunction "4_4") (pintype "passive+no_connect"))
    )
    (net (code "55") (name "unconnected-(P8-Pad5)") (class "Default")
      (node (ref "P8") (pin "5") (pinfunction "5_5") (pintype "passive+no_connect"))
    )
    (net (code "56") (name "unconnected-(P8-Pad6)") (class "Default")
      (node (ref "P8") (pin "6") (pinfunction "6_6") (pintype "passive+no_connect"))
    )
  )
)
